# HoloCubic.net
KiCad netlist of a schematic drawn in EAGLE
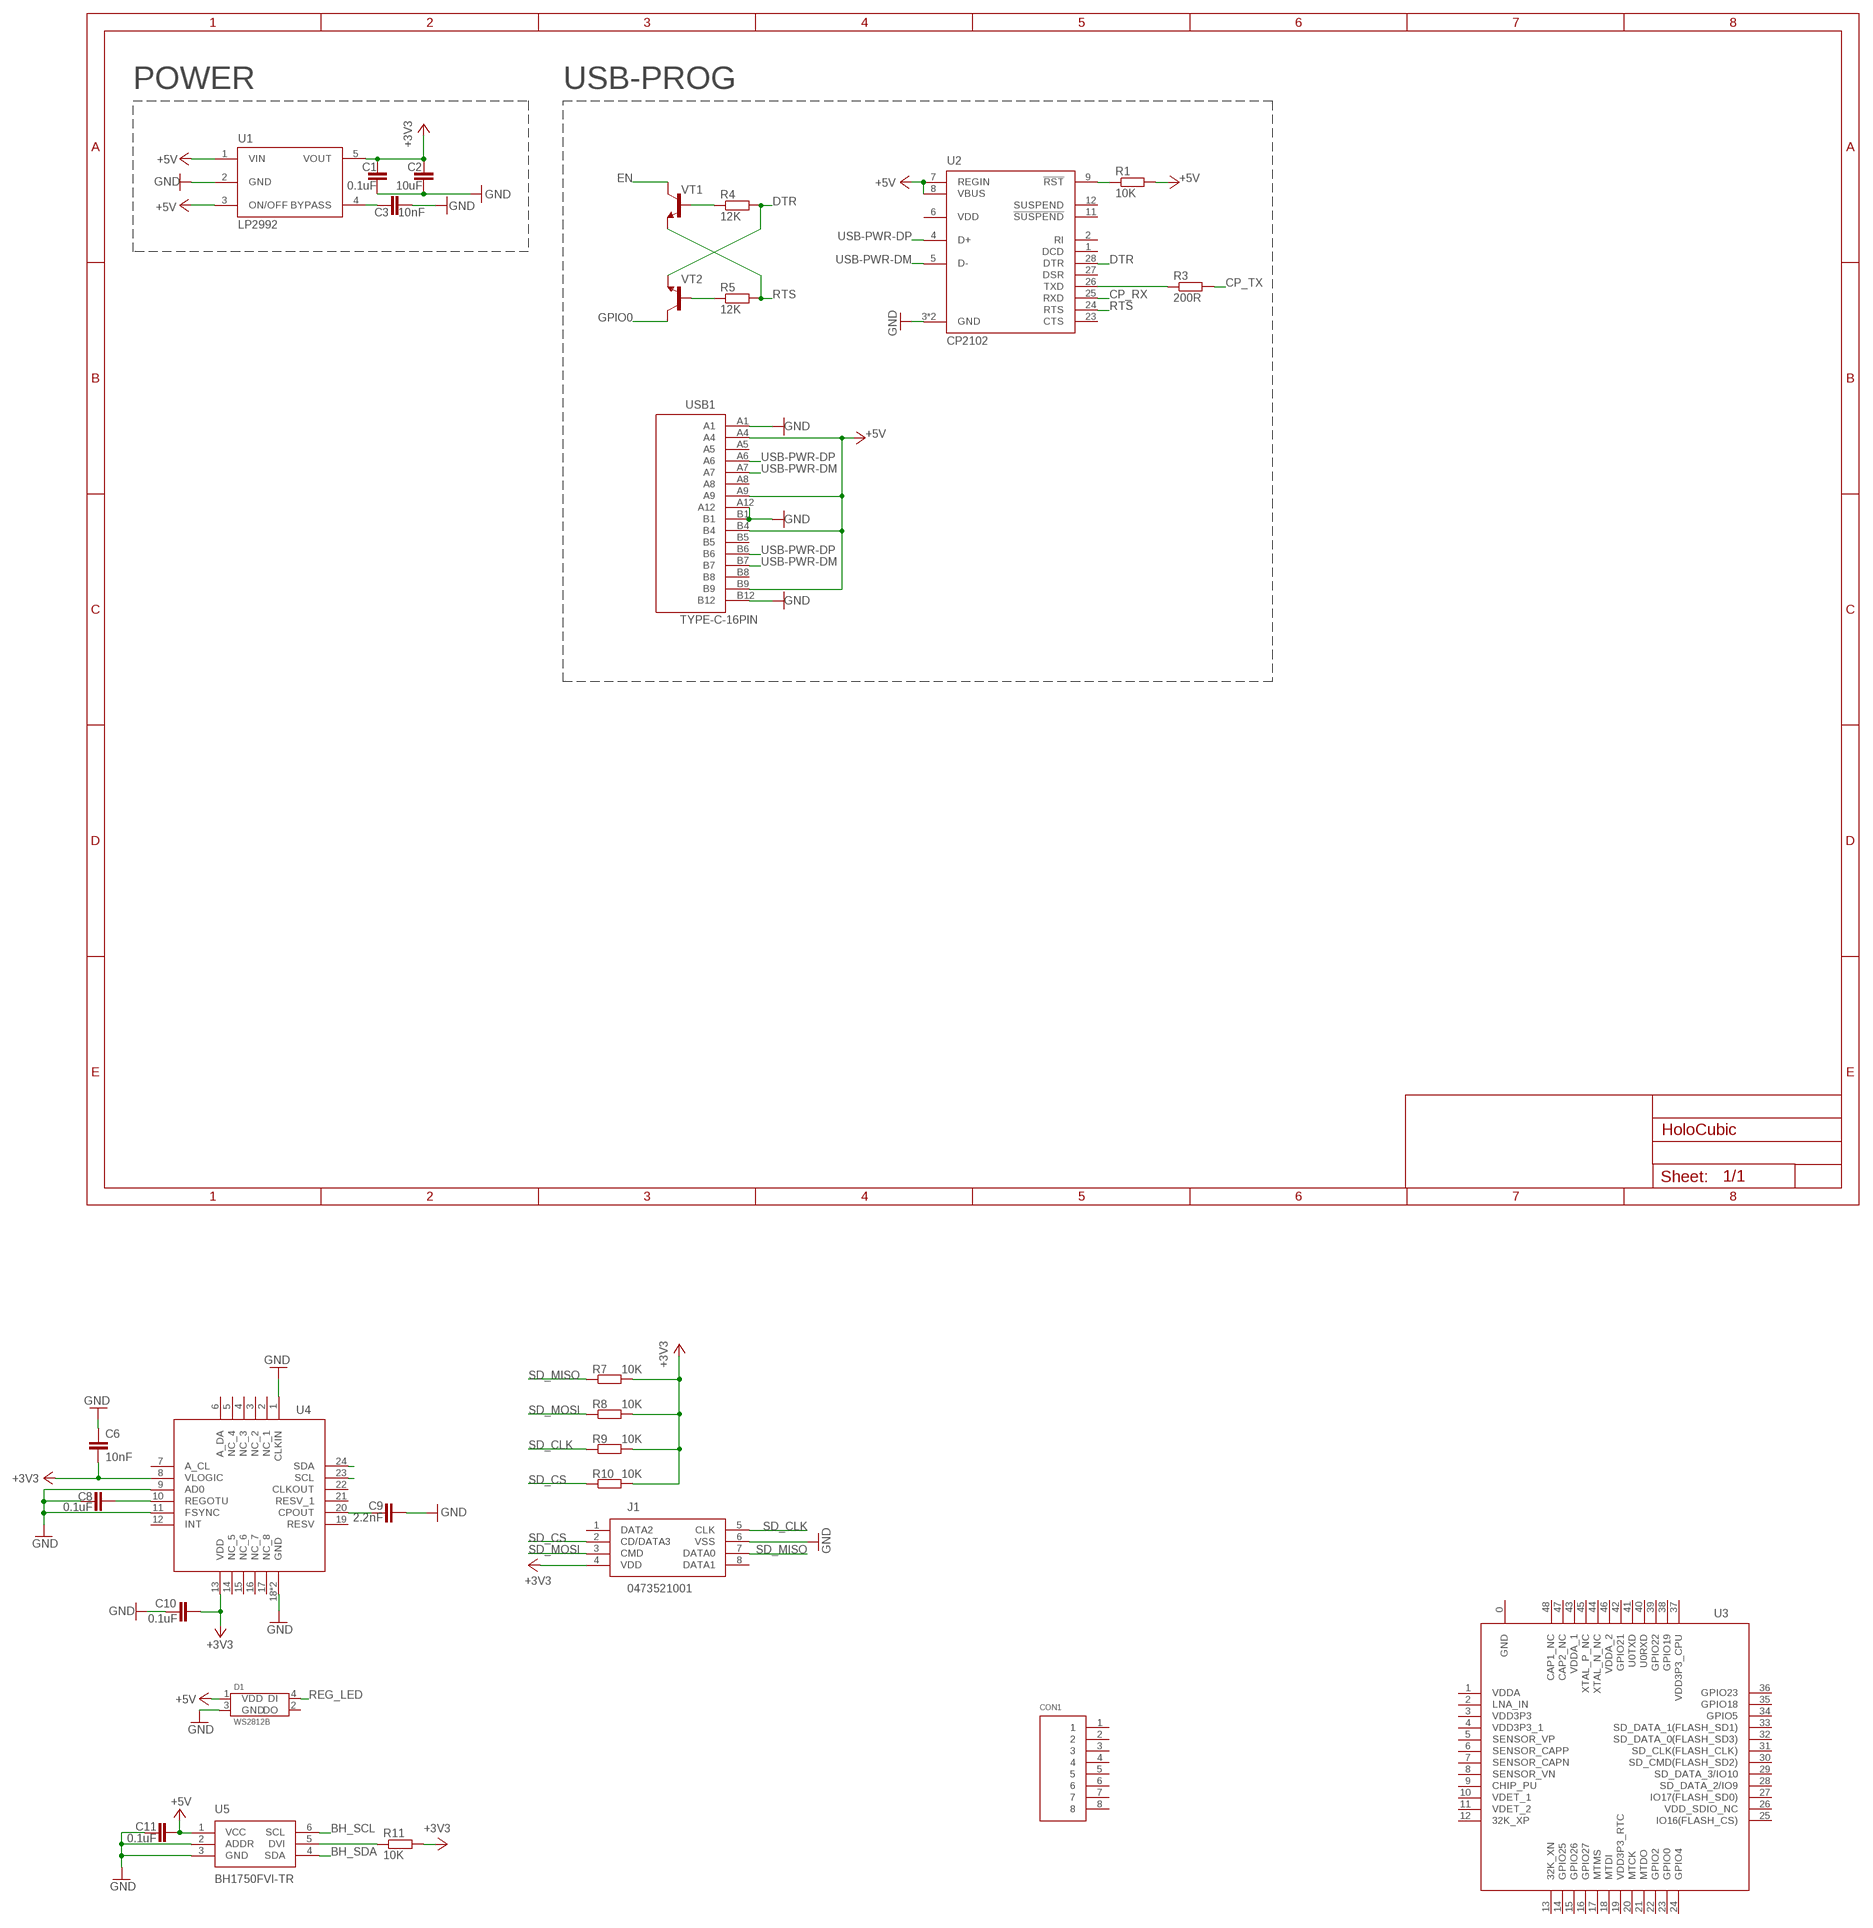
[diagram p0: schematic, sheet 1]

(export (version "E")
  (design (tool "Eeschema 10.0.6"))
  (components
    (comp (ref "C1")
      (value "0.1uF")
      (footprint "eagle-import:C0402")
      (libsource (lib "eagle-import") (part "C-EUC0402"))
    )
    (comp (ref "C2")
      (value "10uF")
      (footprint "eagle-import:C0402")
      (libsource (lib "eagle-import") (part "C-EUC0402"))
    )
    (comp (ref "C3")
      (value "10nF")
      (footprint "eagle-import:C0402")
      (libsource (lib "eagle-import") (part "C-EUC0402"))
    )
    (comp (ref "C6")
      (value "10nF")
      (footprint "eagle-import:C0402")
      (libsource (lib "eagle-import") (part "C-EUC0402"))
    )
    (comp (ref "C8")
      (value "0.1uF")
      (footprint "eagle-import:C0402")
      (libsource (lib "eagle-import") (part "C-EUC0402"))
    )
    (comp (ref "C9")
      (value "2.2nF")
      (footprint "eagle-import:C0402")
      (libsource (lib "eagle-import") (part "C-EUC0402"))
    )
    (comp (ref "C10")
      (value "0.1uF")
      (footprint "eagle-import:C0402")
      (libsource (lib "eagle-import") (part "C-EUC0402"))
    )
    (comp (ref "C11")
      (value "0.1uF")
      (footprint "eagle-import:C0402")
      (libsource (lib "eagle-import") (part "C-EUC0402"))
    )
    (comp (ref "CON1")
      (value "FPC-0.5MM-8P")
      (footprint "eagle-import:FPC-0.5MM-8P")
      (libsource (lib "eagle-import") (part "FPC-0.5MM-8P"))
    )
    (comp (ref "D1")
      (value "WS2812B")
      (footprint "eagle-import:WS2812B")
      (libsource (lib "eagle-import") (part "WS2812B"))
    )
    (comp (ref "J1")
      (value "0473521001")
      (footprint "eagle-import:47352-1001")
      (libsource (lib "eagle-import") (part "0473521001"))
    )
    (comp (ref "R1")
      (value "10K")
      (footprint "eagle-import:R0402")
      (libsource (lib "eagle-import") (part "R-EU_R0402"))
    )
    (comp (ref "R3")
      (value "200R")
      (footprint "eagle-import:R0402")
      (libsource (lib "eagle-import") (part "R-EU_R0402"))
    )
    (comp (ref "R4")
      (value "12K")
      (footprint "eagle-import:R0402")
      (libsource (lib "eagle-import") (part "R-EU_R0402"))
    )
    (comp (ref "R5")
      (value "12K")
      (footprint "eagle-import:R0402")
      (libsource (lib "eagle-import") (part "R-EU_R0402"))
    )
    (comp (ref "R7")
      (value "10K")
      (footprint "eagle-import:R0402")
      (libsource (lib "eagle-import") (part "R-EU_R0402"))
    )
    (comp (ref "R8")
      (value "10K")
      (footprint "eagle-import:R0402")
      (libsource (lib "eagle-import") (part "R-EU_R0402"))
    )
    (comp (ref "R9")
      (value "10K")
      (footprint "eagle-import:R0402")
      (libsource (lib "eagle-import") (part "R-EU_R0402"))
    )
    (comp (ref "R10")
      (value "10K")
      (footprint "eagle-import:R0402")
      (libsource (lib "eagle-import") (part "R-EU_R0402"))
    )
    (comp (ref "R11")
      (value "10K")
      (footprint "eagle-import:R0402")
      (libsource (lib "eagle-import") (part "R-EU_R0402"))
    )
    (comp (ref "U1")
      (value "LP2992")
      (footprint "eagle-import:SOT95P282X145-5N")
      (libsource (lib "eagle-import") (part "LP2992"))
    )
    (comp (ref "U2")
      (value "CP2102")
      (footprint "eagle-import:QFN50P500X500X100-29T315N")
      (libsource (lib "eagle-import") (part "CP2102"))
    )
    (comp (ref "U3")
      (value "ESP32-PICO")
      (footprint "eagle-import:QFN50P700X700X100-49T540N")
      (libsource (lib "eagle-import") (part "ESP32-PICO"))
    )
    (comp (ref "U4")
      (value "MPU6050")
      (footprint "eagle-import:QFN50P400X400X100-25T260N")
      (libsource (lib "eagle-import") (part "MPU6050"))
    )
    (comp (ref "U5")
      (value "BH1750FVI-TR")
      (footprint "eagle-import:WSOF6")
      (fields (field (name "MOUSER_PART_NUMBER") "755-BH1750FVI-TR"))
      (libsource (lib "eagle-import") (part "BH1750FVI-TR"))
    )
    (comp (ref "USB1")
      (value "TYPE-C-16PIN")
      (footprint "eagle-import:TYPE-C-16PIN")
      (libsource (lib "eagle-import") (part "TYPE-C-16PIN"))
    )
    (comp (ref "VT1")
      (value "BC808-NPN-SOT23-BEC")
      (footprint "eagle-import:SOT23-BEC")
      (libsource (lib "eagle-import") (part "-NPN-SOT23-BECBC808"))
    )
    (comp (ref "VT2")
      (value "BC808-NPN-SOT23-BEC")
      (footprint "eagle-import:SOT23-BEC")
      (libsource (lib "eagle-import") (part "-NPN-SOT23-BECBC808"))
    )
  )
  (nets
    (net (code "1") (name "+3V3") (class "Default")
      (node (ref "C1") (pin "1") (pinfunction "1_1") (pintype "passive"))
      (node (ref "C10") (pin "2") (pinfunction "2_2") (pintype "passive"))
      (node (ref "C2") (pin "1") (pinfunction "1_1") (pintype "passive"))
      (node (ref "C6") (pin "2") (pinfunction "2_2") (pintype "passive"))
      (node (ref "J1") (pin "4") (pinfunction "VDD_4") (pintype "bidirectional"))
      (node (ref "R10") (pin "2") (pinfunction "2_2") (pintype "passive"))
      (node (ref "R11") (pin "2") (pinfunction "2_2") (pintype "passive"))
      (node (ref "R7") (pin "2") (pinfunction "2_2") (pintype "passive"))
      (node (ref "R8") (pin "2") (pinfunction "2_2") (pintype "passive"))
      (node (ref "R9") (pin "2") (pinfunction "2_2") (pintype "passive"))
      (node (ref "U1") (pin "5") (pinfunction "VOUT_5") (pintype "bidirectional"))
      (node (ref "U4") (pin "13") (pinfunction "VDD_13") (pintype "bidirectional"))
      (node (ref "U4") (pin "8") (pinfunction "VLOGIC_8") (pintype "bidirectional"))
    )
    (net (code "2") (name "+5V") (class "Default")
      (node (ref "C11") (pin "2") (pinfunction "2_2") (pintype "passive"))
      (node (ref "D1") (pin "1") (pinfunction "VDD_1") (pintype "bidirectional"))
      (node (ref "R1") (pin "2") (pinfunction "2_2") (pintype "passive"))
      (node (ref "U1") (pin "1") (pinfunction "VIN_1") (pintype "bidirectional"))
      (node (ref "U1") (pin "3") (pinfunction "ON/OFF_3") (pintype "bidirectional"))
      (node (ref "U2") (pin "7") (pinfunction "REGIN_7") (pintype "passive"))
      (node (ref "U2") (pin "8") (pinfunction "VBUS_8") (pintype "input"))
      (node (ref "U5") (pin "1") (pinfunction "VCC_1") (pintype "bidirectional"))
      (node (ref "USB1") (pin "A4") (pinfunction "A4_A4") (pintype "bidirectional"))
      (node (ref "USB1") (pin "A9") (pinfunction "A9_A9") (pintype "bidirectional"))
      (node (ref "USB1") (pin "B4") (pinfunction "B4_B4") (pintype "bidirectional"))
      (node (ref "USB1") (pin "B9") (pinfunction "B9_B9") (pintype "bidirectional"))
    )
    (net (code "3") (name "/BH_SCL") (class "Default")
      (node (ref "U5") (pin "6") (pinfunction "SCL_6") (pintype "bidirectional"))
    )
    (net (code "4") (name "/BH_SDA") (class "Default")
      (node (ref "U5") (pin "4") (pinfunction "SDA_4") (pintype "bidirectional"))
    )
    (net (code "5") (name "/CP_RX") (class "Default")
      (node (ref "U2") (pin "25") (pinfunction "RXD_25") (pintype "input"))
    )
    (net (code "6") (name "/CP_TX") (class "Default")
      (node (ref "R3") (pin "2") (pinfunction "2_2") (pintype "passive"))
    )
    (net (code "7") (name "/DTR") (class "Default")
      (node (ref "R4") (pin "2") (pinfunction "2_2") (pintype "passive"))
      (node (ref "U2") (pin "28") (pinfunction "DTR_28") (pintype "output"))
      (node (ref "VT2") (pin "E") (pinfunction "E_E") (pintype "passive"))
    )
    (net (code "8") (name "/EN") (class "Default")
      (node (ref "VT1") (pin "C") (pinfunction "C_C") (pintype "passive"))
    )
    (net (code "9") (name "/GPIO0") (class "Default")
      (node (ref "VT2") (pin "C") (pinfunction "C_C") (pintype "passive"))
    )
    (net (code "10") (name "/REG_LED") (class "Default")
      (node (ref "D1") (pin "4") (pinfunction "DI_4") (pintype "bidirectional"))
    )
    (net (code "11") (name "/RTS") (class "Default")
      (node (ref "R5") (pin "2") (pinfunction "2_2") (pintype "passive"))
      (node (ref "U2") (pin "24") (pinfunction "RTS_24") (pintype "output"))
      (node (ref "VT1") (pin "E") (pinfunction "E_E") (pintype "passive"))
    )
    (net (code "12") (name "/SD_CLK") (class "Default")
      (node (ref "J1") (pin "5") (pinfunction "CLK_5") (pintype "bidirectional"))
      (node (ref "R9") (pin "1") (pinfunction "1_1") (pintype "passive"))
    )
    (net (code "13") (name "/SD_CS") (class "Default")
      (node (ref "J1") (pin "2") (pinfunction "CD/DATA3_2") (pintype "bidirectional"))
      (node (ref "R10") (pin "1") (pinfunction "1_1") (pintype "passive"))
    )
    (net (code "14") (name "/SD_MISO") (class "Default")
      (node (ref "J1") (pin "7") (pinfunction "DATA0_7") (pintype "bidirectional"))
      (node (ref "R7") (pin "1") (pinfunction "1_1") (pintype "passive"))
    )
    (net (code "15") (name "/SD_MOSI") (class "Default")
      (node (ref "J1") (pin "3") (pinfunction "CMD_3") (pintype "bidirectional"))
      (node (ref "R8") (pin "1") (pinfunction "1_1") (pintype "passive"))
    )
    (net (code "16") (name "/USB-PWR-DM") (class "Default")
      (node (ref "U2") (pin "5") (pinfunction "D-_5") (pintype "bidirectional"))
      (node (ref "USB1") (pin "A7") (pinfunction "A7_A7") (pintype "bidirectional"))
      (node (ref "USB1") (pin "B7") (pinfunction "B7_B7") (pintype "bidirectional"))
    )
    (net (code "17") (name "/USB-PWR-DP") (class "Default")
      (node (ref "U2") (pin "4") (pinfunction "D+_4") (pintype "bidirectional"))
      (node (ref "USB1") (pin "A6") (pinfunction "A6_A6") (pintype "bidirectional"))
      (node (ref "USB1") (pin "B6") (pinfunction "B6_B6") (pintype "bidirectional"))
    )
    (net (code "18") (name "/VDD") (class "Default")
      (node (ref "U2") (pin "6") (pinfunction "VDD_6") (pintype "power_in"))
    )
    (net (code "19") (name "GND") (class "Default")
      (node (ref "C1") (pin "2") (pinfunction "2_2") (pintype "passive"))
      (node (ref "C10") (pin "1") (pinfunction "1_1") (pintype "passive"))
      (node (ref "C11") (pin "1") (pinfunction "1_1") (pintype "passive"))
      (node (ref "C2") (pin "2") (pinfunction "2_2") (pintype "passive"))
      (node (ref "C3") (pin "2") (pinfunction "2_2") (pintype "passive"))
      (node (ref "C6") (pin "1") (pinfunction "1_1") (pintype "passive"))
      (node (ref "C8") (pin "1") (pinfunction "1_1") (pintype "passive"))
      (node (ref "C9") (pin "2") (pinfunction "2_2") (pintype "passive"))
      (node (ref "D1") (pin "3") (pinfunction "GND_3") (pintype "bidirectional"))
      (node (ref "J1") (pin "6") (pinfunction "VSS_6") (pintype "bidirectional"))
      (node (ref "U1") (pin "2") (pinfunction "GND_2") (pintype "bidirectional"))
      (node (ref "U2") (pin "29") (pinfunction "GND_29") (pintype "power_in"))
      (node (ref "U2") (pin "3") (pinfunction "GND_3") (pintype "power_in"))
      (node (ref "U4") (pin "1") (pinfunction "CLKIN_1") (pintype "bidirectional"))
      (node (ref "U4") (pin "11") (pinfunction "FSYNC_11") (pintype "bidirectional"))
      (node (ref "U4") (pin "18") (pinfunction "GND_18") (pintype "bidirectional"))
      (node (ref "U4") (pin "25") (pinfunction "GND_25") (pintype "bidirectional"))
      (node (ref "U4") (pin "9") (pinfunction "AD0_9") (pintype "bidirectional"))
      (node (ref "U5") (pin "2") (pinfunction "ADDR_2") (pintype "bidirectional"))
      (node (ref "U5") (pin "3") (pinfunction "GND_3") (pintype "bidirectional"))
      (node (ref "USB1") (pin "A1") (pinfunction "A1_A1") (pintype "bidirectional"))
      (node (ref "USB1") (pin "A12") (pinfunction "A12_A12") (pintype "bidirectional"))
      (node (ref "USB1") (pin "B1") (pinfunction "B1_B1") (pintype "bidirectional"))
      (node (ref "USB1") (pin "B12") (pinfunction "B12_B12") (pintype "bidirectional"))
    )
    (net (code "20") (name "Net-(R4-Pad1)") (class "Default")
      (node (ref "R4") (pin "1") (pinfunction "1_1") (pintype "passive"))
      (node (ref "VT1") (pin "B") (pinfunction "B_B") (pintype "passive"))
    )
    (net (code "21") (name "Net-(R5-Pad1)") (class "Default")
      (node (ref "R5") (pin "1") (pinfunction "1_1") (pintype "passive"))
      (node (ref "VT2") (pin "B") (pinfunction "B_B") (pintype "passive"))
    )
    (net (code "22") (name "Net-(U1-BYPASS)") (class "Default")
      (node (ref "C3") (pin "1") (pinfunction "1_1") (pintype "passive"))
      (node (ref "U1") (pin "4") (pinfunction "BYPASS_4") (pintype "bidirectional"))
    )
    (net (code "23") (name "Net-(U2-TXD)") (class "Default")
      (node (ref "R3") (pin "1") (pinfunction "1_1") (pintype "passive"))
      (node (ref "U2") (pin "26") (pinfunction "TXD_26") (pintype "output"))
    )
    (net (code "24") (name "Net-(U2-~{RST})") (class "Default")
      (node (ref "R1") (pin "1") (pinfunction "1_1") (pintype "passive"))
      (node (ref "U2") (pin "9") (pinfunction "~{RST}_9") (pintype "bidirectional"))
    )
    (net (code "25") (name "Net-(U4-CPOUT)") (class "Default")
      (node (ref "C9") (pin "1") (pinfunction "1_1") (pintype "passive"))
      (node (ref "U4") (pin "20") (pinfunction "CPOUT_20") (pintype "bidirectional"))
    )
    (net (code "26") (name "Net-(U4-REGOTU)") (class "Default")
      (node (ref "C8") (pin "2") (pinfunction "2_2") (pintype "passive"))
      (node (ref "U4") (pin "10") (pinfunction "REGOTU_10") (pintype "bidirectional"))
    )
    (net (code "27") (name "Net-(U5-DVI)") (class "Default")
      (node (ref "R11") (pin "1") (pinfunction "1_1") (pintype "passive"))
      (node (ref "U5") (pin "5") (pinfunction "DVI_5") (pintype "bidirectional"))
    )
    (net (code "28") (name "unconnected-(CON1-Pad1)") (class "Default")
      (node (ref "CON1") (pin "1") (pinfunction "1_1") (pintype "bidirectional"))
    )
    (net (code "29") (name "unconnected-(CON1-Pad2)") (class "Default")
      (node (ref "CON1") (pin "2") (pinfunction "2_2") (pintype "bidirectional"))
    )
    (net (code "30") (name "unconnected-(CON1-Pad3)") (class "Default")
      (node (ref "CON1") (pin "3") (pinfunction "3_3") (pintype "bidirectional"))
    )
    (net (code "31") (name "unconnected-(CON1-Pad4)") (class "Default")
      (node (ref "CON1") (pin "4") (pinfunction "4_4") (pintype "bidirectional"))
    )
    (net (code "32") (name "unconnected-(CON1-Pad5)") (class "Default")
      (node (ref "CON1") (pin "5") (pinfunction "5_5") (pintype "bidirectional"))
    )
    (net (code "33") (name "unconnected-(CON1-Pad6)") (class "Default")
      (node (ref "CON1") (pin "6") (pinfunction "6_6") (pintype "bidirectional"))
    )
    (net (code "34") (name "unconnected-(CON1-Pad7)") (class "Default")
      (node (ref "CON1") (pin "7") (pinfunction "7_7") (pintype "bidirectional"))
    )
    (net (code "35") (name "unconnected-(CON1-Pad8)") (class "Default")
      (node (ref "CON1") (pin "8") (pinfunction "8_8") (pintype "bidirectional"))
    )
    (net (code "36") (name "unconnected-(D1-DO-Pad2)") (class "Default")
      (node (ref "D1") (pin "2") (pinfunction "DO_2") (pintype "bidirectional"))
    )
    (net (code "37") (name "unconnected-(J1-DATA1-Pad8)") (class "Default")
      (node (ref "J1") (pin "8") (pinfunction "DATA1_8") (pintype "bidirectional"))
    )
    (net (code "38") (name "unconnected-(J1-DATA2-Pad1)") (class "Default")
      (node (ref "J1") (pin "1") (pinfunction "DATA2_1") (pintype "bidirectional"))
    )
    (net (code "39") (name "unconnected-(U2-CTS-Pad23)") (class "Default")
      (node (ref "U2") (pin "23") (pinfunction "CTS_23") (pintype "input"))
    )
    (net (code "40") (name "unconnected-(U2-DCD-Pad1)") (class "Default")
      (node (ref "U2") (pin "1") (pinfunction "DCD_1") (pintype "input"))
    )
    (net (code "41") (name "unconnected-(U2-DSR-Pad27)") (class "Default")
      (node (ref "U2") (pin "27") (pinfunction "DSR_27") (pintype "input"))
    )
    (net (code "42") (name "unconnected-(U2-RI-Pad2)") (class "Default")
      (node (ref "U2") (pin "2") (pinfunction "RI_2") (pintype "input"))
    )
    (net (code "43") (name "unconnected-(U2-SUSPEND-Pad12)") (class "Default")
      (node (ref "U2") (pin "12") (pinfunction "SUSPEND_12") (pintype "output"))
    )
    (net (code "44") (name "unconnected-(U2-~{SUSPEND}-Pad11)") (class "Default")
      (node (ref "U2") (pin "11") (pinfunction "~{SUSPEND}_11") (pintype "output"))
    )
    (net (code "45") (name "unconnected-(U3-32K_XN-Pad13)") (class "Default")
      (node (ref "U3") (pin "13") (pinfunction "32K_XN_13") (pintype "bidirectional"))
    )
    (net (code "46") (name "unconnected-(U3-32K_XP-Pad12)") (class "Default")
      (node (ref "U3") (pin "12") (pinfunction "32K_XP_12") (pintype "bidirectional"))
    )
    (net (code "47") (name "unconnected-(U3-CAP1_NC-Pad48)") (class "Default")
      (node (ref "U3") (pin "48") (pinfunction "CAP1_NC_48") (pintype "bidirectional"))
    )
    (net (code "48") (name "unconnected-(U3-CAP2_NC-Pad47)") (class "Default")
      (node (ref "U3") (pin "47") (pinfunction "CAP2_NC_47") (pintype "bidirectional"))
    )
    (net (code "49") (name "unconnected-(U3-CHIP_PU-Pad9)") (class "Default")
      (node (ref "U3") (pin "9") (pinfunction "CHIP_PU_9") (pintype "bidirectional"))
    )
    (net (code "50") (name "unconnected-(U3-GND-Pad0)") (class "Default")
      (node (ref "U3") (pin "0") (pinfunction "GND_0") (pintype "bidirectional"))
    )
    (net (code "51") (name "unconnected-(U3-GPIO0-Pad23)") (class "Default")
      (node (ref "U3") (pin "23") (pinfunction "GPIO0_23") (pintype "bidirectional"))
    )
    (net (code "52") (name "unconnected-(U3-GPIO2-Pad22)") (class "Default")
      (node (ref "U3") (pin "22") (pinfunction "GPIO2_22") (pintype "bidirectional"))
    )
    (net (code "53") (name "unconnected-(U3-GPIO4-Pad24)") (class "Default")
      (node (ref "U3") (pin "24") (pinfunction "GPIO4_24") (pintype "bidirectional"))
    )
    (net (code "54") (name "unconnected-(U3-GPIO5-Pad34)") (class "Default")
      (node (ref "U3") (pin "34") (pinfunction "GPIO5_34") (pintype "bidirectional"))
    )
    (net (code "55") (name "unconnected-(U3-GPIO18-Pad35)") (class "Default")
      (node (ref "U3") (pin "35") (pinfunction "GPIO18_35") (pintype "bidirectional"))
    )
    (net (code "56") (name "unconnected-(U3-GPIO19-Pad38)") (class "Default")
      (node (ref "U3") (pin "38") (pinfunction "GPIO19_38") (pintype "bidirectional"))
    )
    (net (code "57") (name "unconnected-(U3-GPIO21-Pad42)") (class "Default")
      (node (ref "U3") (pin "42") (pinfunction "GPIO21_42") (pintype "bidirectional"))
    )
    (net (code "58") (name "unconnected-(U3-GPIO22-Pad39)") (class "Default")
      (node (ref "U3") (pin "39") (pinfunction "GPIO22_39") (pintype "bidirectional"))
    )
    (net (code "59") (name "unconnected-(U3-GPIO23-Pad36)") (class "Default")
      (node (ref "U3") (pin "36") (pinfunction "GPIO23_36") (pintype "bidirectional"))
    )
    (net (code "60") (name "unconnected-(U3-GPIO25-Pad14)") (class "Default")
      (node (ref "U3") (pin "14") (pinfunction "GPIO25_14") (pintype "bidirectional"))
    )
    (net (code "61") (name "unconnected-(U3-GPIO26-Pad15)") (class "Default")
      (node (ref "U3") (pin "15") (pinfunction "GPIO26_15") (pintype "bidirectional"))
    )
    (net (code "62") (name "unconnected-(U3-GPIO27-Pad16)") (class "Default")
      (node (ref "U3") (pin "16") (pinfunction "GPIO27_16") (pintype "bidirectional"))
    )
    (net (code "63") (name "unconnected-(U3-IO16(FLASH_CS)-Pad25)") (class "Default")
      (node (ref "U3") (pin "25") (pinfunction "IO16(FLASH_CS)_25") (pintype "bidirectional"))
    )
    (net (code "64") (name "unconnected-(U3-IO17(FLASH_SD0)-Pad27)") (class "Default")
      (node (ref "U3") (pin "27") (pinfunction "IO17(FLASH_SD0)_27") (pintype "bidirectional"))
    )
    (net (code "65") (name "unconnected-(U3-LNA_IN-Pad2)") (class "Default")
      (node (ref "U3") (pin "2") (pinfunction "LNA_IN_2") (pintype "bidirectional"))
    )
    (net (code "66") (name "unconnected-(U3-MTCK-Pad20)") (class "Default")
      (node (ref "U3") (pin "20") (pinfunction "MTCK_20") (pintype "bidirectional"))
    )
    (net (code "67") (name "unconnected-(U3-MTDI-Pad18)") (class "Default")
      (node (ref "U3") (pin "18") (pinfunction "MTDI_18") (pintype "bidirectional"))
    )
    (net (code "68") (name "unconnected-(U3-MTDO-Pad21)") (class "Default")
      (node (ref "U3") (pin "21") (pinfunction "MTDO_21") (pintype "bidirectional"))
    )
    (net (code "69") (name "unconnected-(U3-MTMS-Pad17)") (class "Default")
      (node (ref "U3") (pin "17") (pinfunction "MTMS_17") (pintype "bidirectional"))
    )
    (net (code "70") (name "unconnected-(U3-SD_CLK(FLASH_CLK)-Pad31)") (class "Default")
      (node (ref "U3") (pin "31") (pinfunction "SD_CLK(FLASH_CLK)_31") (pintype "bidirectional"))
    )
    (net (code "71") (name "unconnected-(U3-SD_CMD(FLASH_SD2)-Pad30)") (class "Default")
      (node (ref "U3") (pin "30") (pinfunction "SD_CMD(FLASH_SD2)_30") (pintype "bidirectional"))
    )
    (net (code "72") (name "unconnected-(U3-SD_DATA_0(FLASH_SD3)-Pad32)") (class "Default")
      (node (ref "U3") (pin "32") (pinfunction "SD_DATA_0(FLASH_SD3)_32") (pintype "bidirectional"))
    )
    (net (code "73") (name "unconnected-(U3-SD_DATA_1(FLASH_SD1)-Pad33)") (class "Default")
      (node (ref "U3") (pin "33") (pinfunction "SD_DATA_1(FLASH_SD1)_33") (pintype "bidirectional"))
    )
    (net (code "74") (name "unconnected-(U3-SD_DATA_2{slash}IO9-Pad28)") (class "Default")
      (node (ref "U3") (pin "28") (pinfunction "SD_DATA_2/IO9_28") (pintype "bidirectional"))
    )
    (net (code "75") (name "unconnected-(U3-SD_DATA_3{slash}IO10-Pad29)") (class "Default")
      (node (ref "U3") (pin "29") (pinfunction "SD_DATA_3/IO10_29") (pintype "bidirectional"))
    )
    (net (code "76") (name "unconnected-(U3-SENSOR_CAPN-Pad7)") (class "Default")
      (node (ref "U3") (pin "7") (pinfunction "SENSOR_CAPN_7") (pintype "bidirectional"))
    )
    (net (code "77") (name "unconnected-(U3-SENSOR_CAPP-Pad6)") (class "Default")
      (node (ref "U3") (pin "6") (pinfunction "SENSOR_CAPP_6") (pintype "bidirectional"))
    )
    (net (code "78") (name "unconnected-(U3-SENSOR_VN-Pad8)") (class "Default")
      (node (ref "U3") (pin "8") (pinfunction "SENSOR_VN_8") (pintype "bidirectional"))
    )
    (net (code "79") (name "unconnected-(U3-SENSOR_VP-Pad5)") (class "Default")
      (node (ref "U3") (pin "5") (pinfunction "SENSOR_VP_5") (pintype "bidirectional"))
    )
    (net (code "80") (name "unconnected-(U3-U0RXD-Pad40)") (class "Default")
      (node (ref "U3") (pin "40") (pinfunction "U0RXD_40") (pintype "bidirectional"))
    )
    (net (code "81") (name "unconnected-(U3-U0TXD-Pad41)") (class "Default")
      (node (ref "U3") (pin "41") (pinfunction "U0TXD_41") (pintype "bidirectional"))
    )
    (net (code "82") (name "unconnected-(U3-VDD3P3-Pad3)") (class "Default")
      (node (ref "U3") (pin "3") (pinfunction "VDD3P3_3") (pintype "bidirectional"))
    )
    (net (code "83") (name "unconnected-(U3-VDD3P3_1-Pad4)") (class "Default")
      (node (ref "U3") (pin "4") (pinfunction "VDD3P3_1_4") (pintype "bidirectional"))
    )
    (net (code "84") (name "unconnected-(U3-VDD3P3_CPU-Pad37)") (class "Default")
      (node (ref "U3") (pin "37") (pinfunction "VDD3P3_CPU_37") (pintype "bidirectional"))
    )
    (net (code "85") (name "unconnected-(U3-VDD3P3_RTC-Pad19)") (class "Default")
      (node (ref "U3") (pin "19") (pinfunction "VDD3P3_RTC_19") (pintype "bidirectional"))
    )
    (net (code "86") (name "unconnected-(U3-VDDA-Pad1)") (class "Default")
      (node (ref "U3") (pin "1") (pinfunction "VDDA_1") (pintype "bidirectional"))
    )
    (net (code "87") (name "unconnected-(U3-VDDA_1-Pad43)") (class "Default")
      (node (ref "U3") (pin "43") (pinfunction "VDDA_1_43") (pintype "bidirectional"))
    )
    (net (code "88") (name "unconnected-(U3-VDDA_2-Pad46)") (class "Default")
      (node (ref "U3") (pin "46") (pinfunction "VDDA_2_46") (pintype "bidirectional"))
    )
    (net (code "89") (name "unconnected-(U3-VDD_SDIO_NC-Pad26)") (class "Default")
      (node (ref "U3") (pin "26") (pinfunction "VDD_SDIO_NC_26") (pintype "bidirectional"))
    )
    (net (code "90") (name "unconnected-(U3-VDET_1-Pad10)") (class "Default")
      (node (ref "U3") (pin "10") (pinfunction "VDET_1_10") (pintype "bidirectional"))
    )
    (net (code "91") (name "unconnected-(U3-VDET_2-Pad11)") (class "Default")
      (node (ref "U3") (pin "11") (pinfunction "VDET_2_11") (pintype "bidirectional"))
    )
    (net (code "92") (name "unconnected-(U3-XTAL_N_NC-Pad44)") (class "Default")
      (node (ref "U3") (pin "44") (pinfunction "XTAL_N_NC_44") (pintype "bidirectional"))
    )
    (net (code "93") (name "unconnected-(U3-XTAL_P_NC-Pad45)") (class "Default")
      (node (ref "U3") (pin "45") (pinfunction "XTAL_P_NC_45") (pintype "bidirectional"))
    )
    (net (code "94") (name "unconnected-(U4-A_CL-Pad7)") (class "Default")
      (node (ref "U4") (pin "7") (pinfunction "A_CL_7") (pintype "bidirectional"))
    )
    (net (code "95") (name "unconnected-(U4-A_DA-Pad6)") (class "Default")
      (node (ref "U4") (pin "6") (pinfunction "A_DA_6") (pintype "bidirectional"))
    )
    (net (code "96") (name "unconnected-(U4-CLKOUT-Pad22)") (class "Default")
      (node (ref "U4") (pin "22") (pinfunction "CLKOUT_22") (pintype "bidirectional"))
    )
    (net (code "97") (name "unconnected-(U4-INT-Pad12)") (class "Default")
      (node (ref "U4") (pin "12") (pinfunction "INT_12") (pintype "bidirectional"))
    )
    (net (code "98") (name "unconnected-(U4-NC_1-Pad2)") (class "Default")
      (node (ref "U4") (pin "2") (pinfunction "NC_1_2") (pintype "bidirectional"))
    )
    (net (code "99") (name "unconnected-(U4-NC_2-Pad3)") (class "Default")
      (node (ref "U4") (pin "3") (pinfunction "NC_2_3") (pintype "bidirectional"))
    )
    (net (code "100") (name "unconnected-(U4-NC_3-Pad4)") (class "Default")
      (node (ref "U4") (pin "4") (pinfunction "NC_3_4") (pintype "bidirectional"))
    )
    (net (code "101") (name "unconnected-(U4-NC_4-Pad5)") (class "Default")
      (node (ref "U4") (pin "5") (pinfunction "NC_4_5") (pintype "bidirectional"))
    )
    (net (code "102") (name "unconnected-(U4-NC_5-Pad14)") (class "Default")
      (node (ref "U4") (pin "14") (pinfunction "NC_5_14") (pintype "bidirectional"))
    )
    (net (code "103") (name "unconnected-(U4-NC_6-Pad15)") (class "Default")
      (node (ref "U4") (pin "15") (pinfunction "NC_6_15") (pintype "bidirectional"))
    )
    (net (code "104") (name "unconnected-(U4-NC_7-Pad16)") (class "Default")
      (node (ref "U4") (pin "16") (pinfunction "NC_7_16") (pintype "bidirectional"))
    )
    (net (code "105") (name "unconnected-(U4-NC_8-Pad17)") (class "Default")
      (node (ref "U4") (pin "17") (pinfunction "NC_8_17") (pintype "bidirectional"))
    )
    (net (code "106") (name "unconnected-(U4-RESV-Pad19)") (class "Default")
      (node (ref "U4") (pin "19") (pinfunction "RESV_19") (pintype "bidirectional"))
    )
    (net (code "107") (name "unconnected-(U4-RESV_1-Pad21)") (class "Default")
      (node (ref "U4") (pin "21") (pinfunction "RESV_1_21") (pintype "bidirectional"))
    )
    (net (code "108") (name "unconnected-(U4-SCL-Pad23)") (class "Default")
      (node (ref "U4") (pin "23") (pinfunction "SCL_23") (pintype "bidirectional"))
    )
    (net (code "109") (name "unconnected-(U4-SDA-Pad24)") (class "Default")
      (node (ref "U4") (pin "24") (pinfunction "SDA_24") (pintype "bidirectional"))
    )
    (net (code "110") (name "unconnected-(USB1-PadA5)") (class "Default")
      (node (ref "USB1") (pin "A5") (pinfunction "A5_A5") (pintype "bidirectional"))
    )
    (net (code "111") (name "unconnected-(USB1-PadA8)") (class "Default")
      (node (ref "USB1") (pin "A8") (pinfunction "A8_A8") (pintype "bidirectional"))
    )
    (net (code "112") (name "unconnected-(USB1-PadB5)") (class "Default")
      (node (ref "USB1") (pin "B5") (pinfunction "B5_B5") (pintype "bidirectional"))
    )
    (net (code "113") (name "unconnected-(USB1-PadB8)") (class "Default")
      (node (ref "USB1") (pin "B8") (pinfunction "B8_B8") (pintype "bidirectional"))
    )
  )
)
